# Calciatore_Rev_2_UP.net
KiCad netlist of a schematic drawn in EAGLE
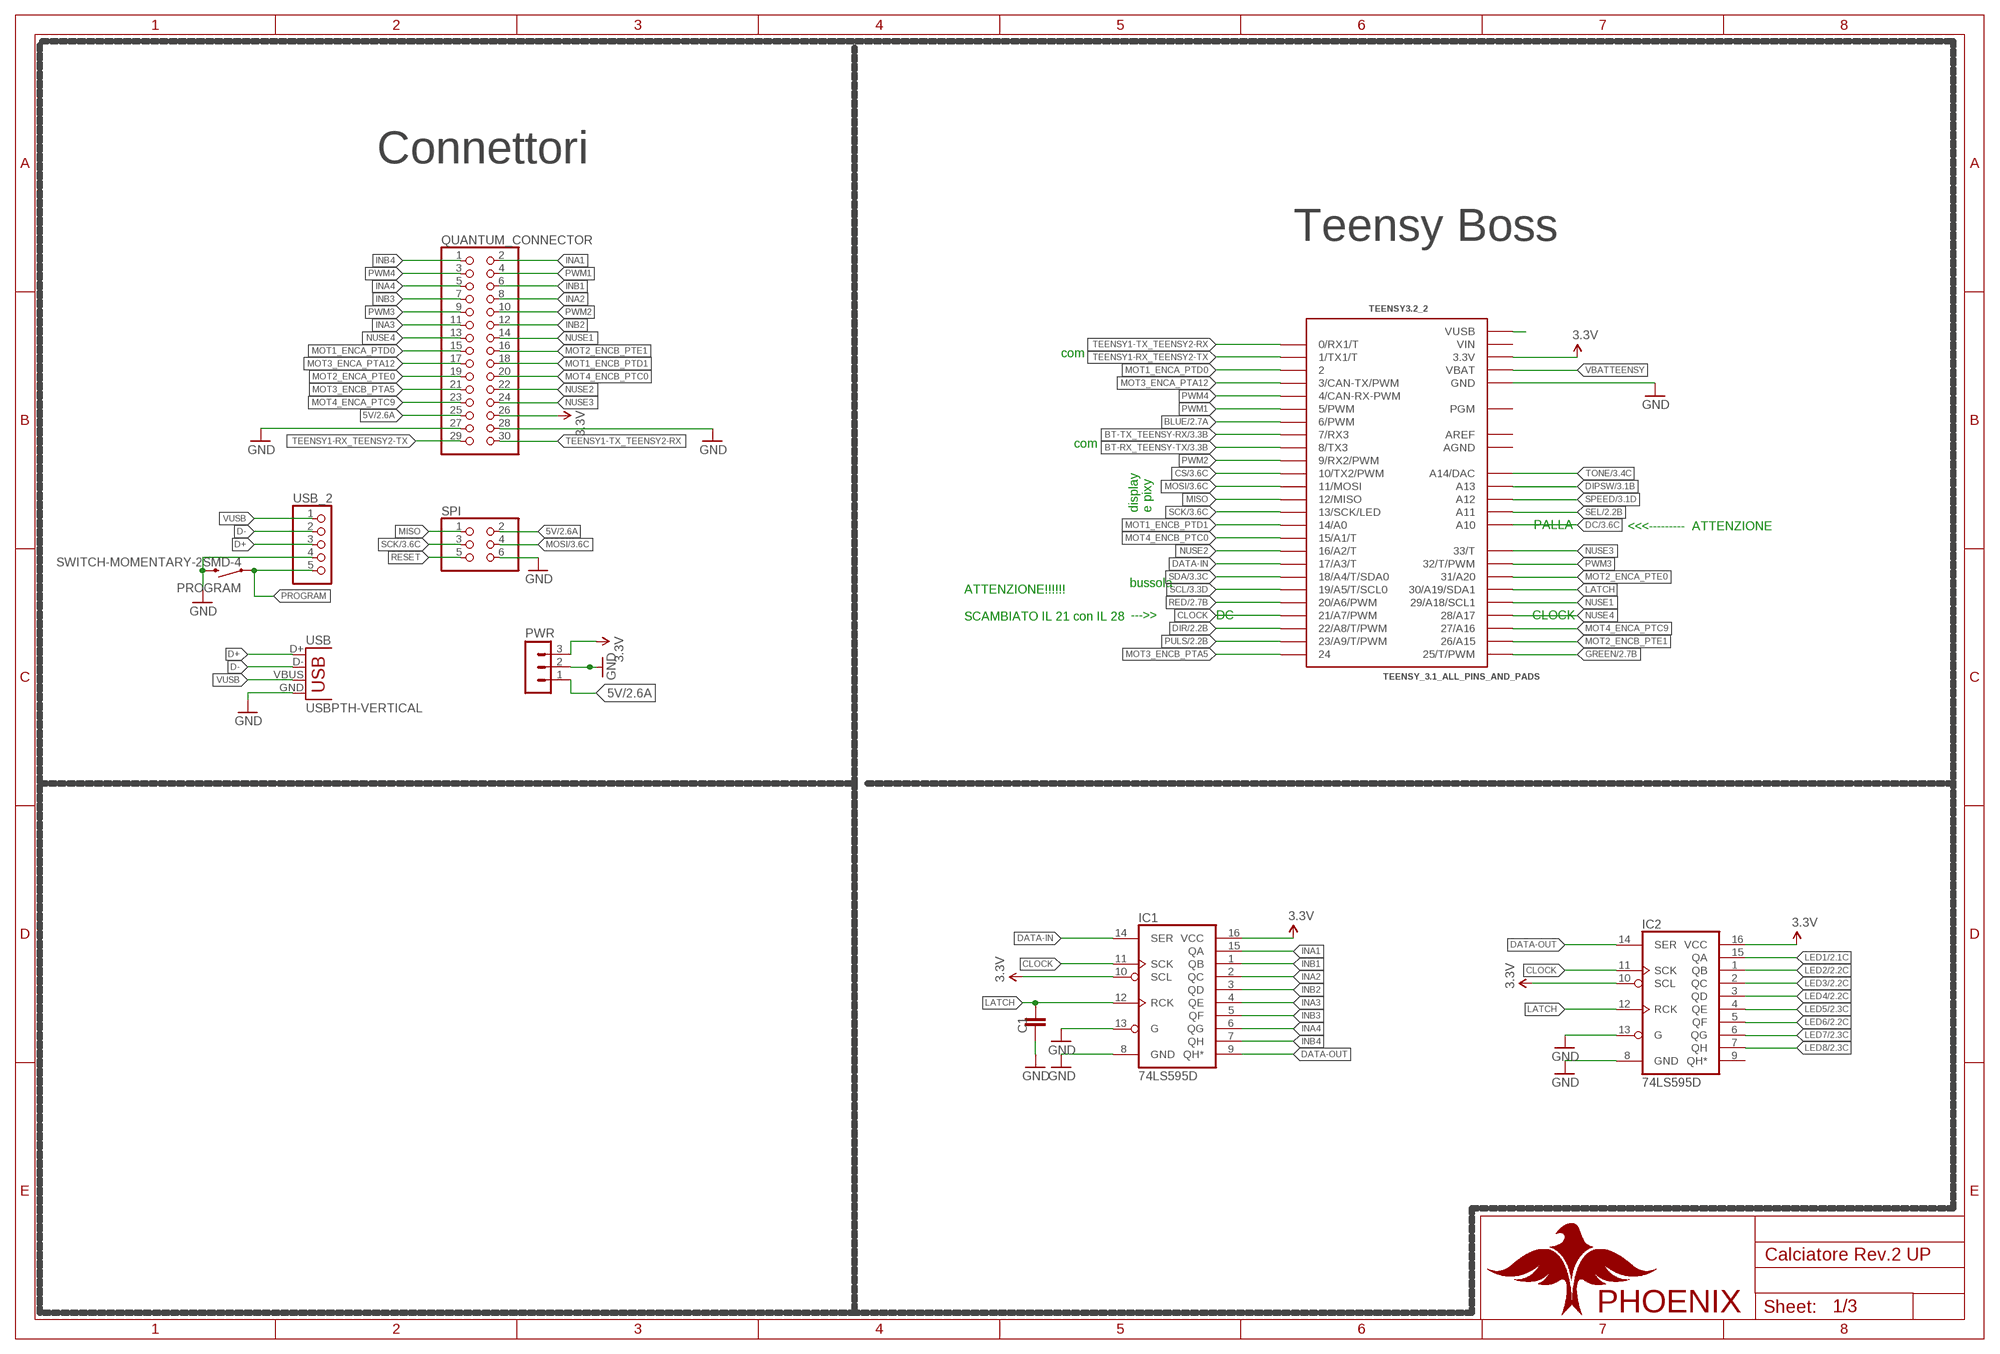
[diagram p0: schematic, sheet 1]
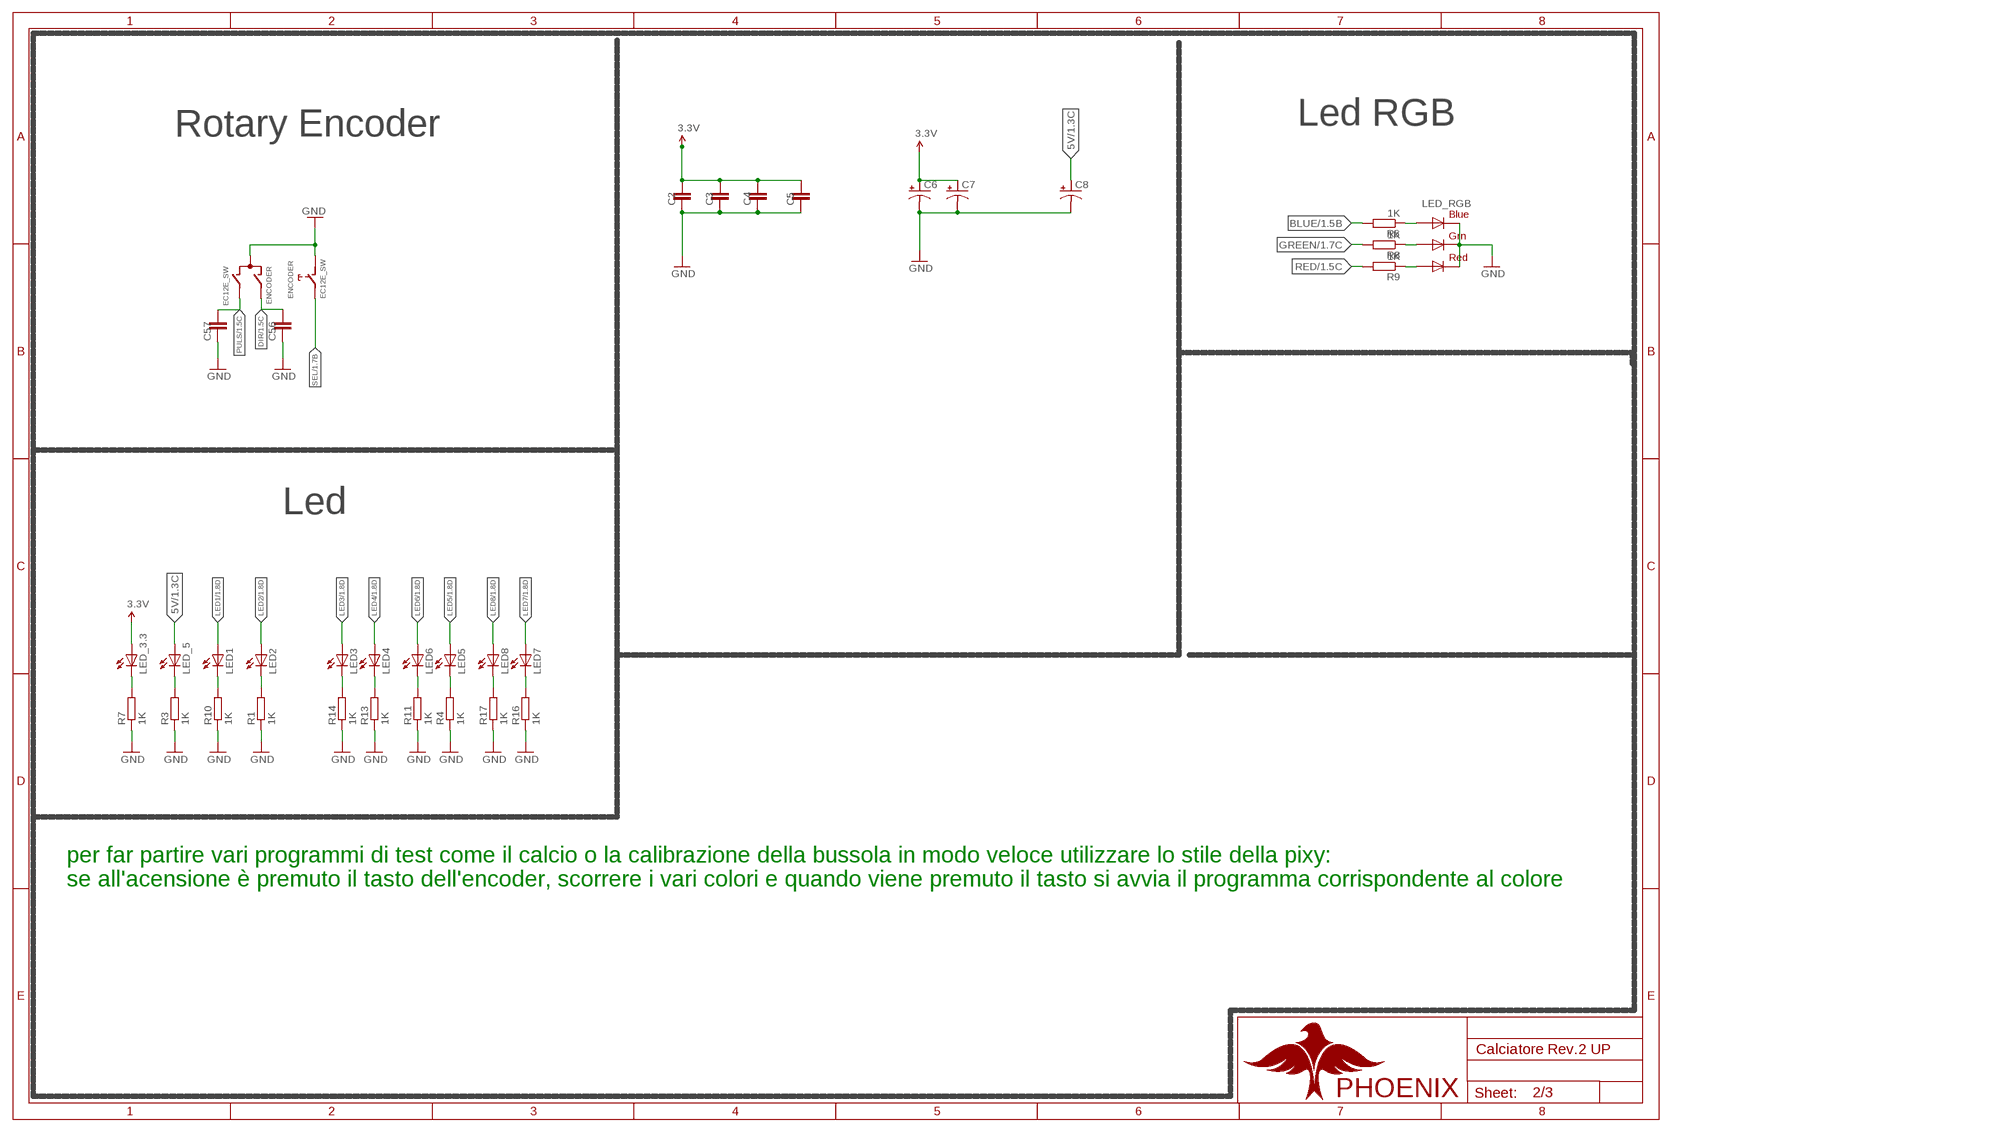
[diagram p1: schematic, sheet 2]
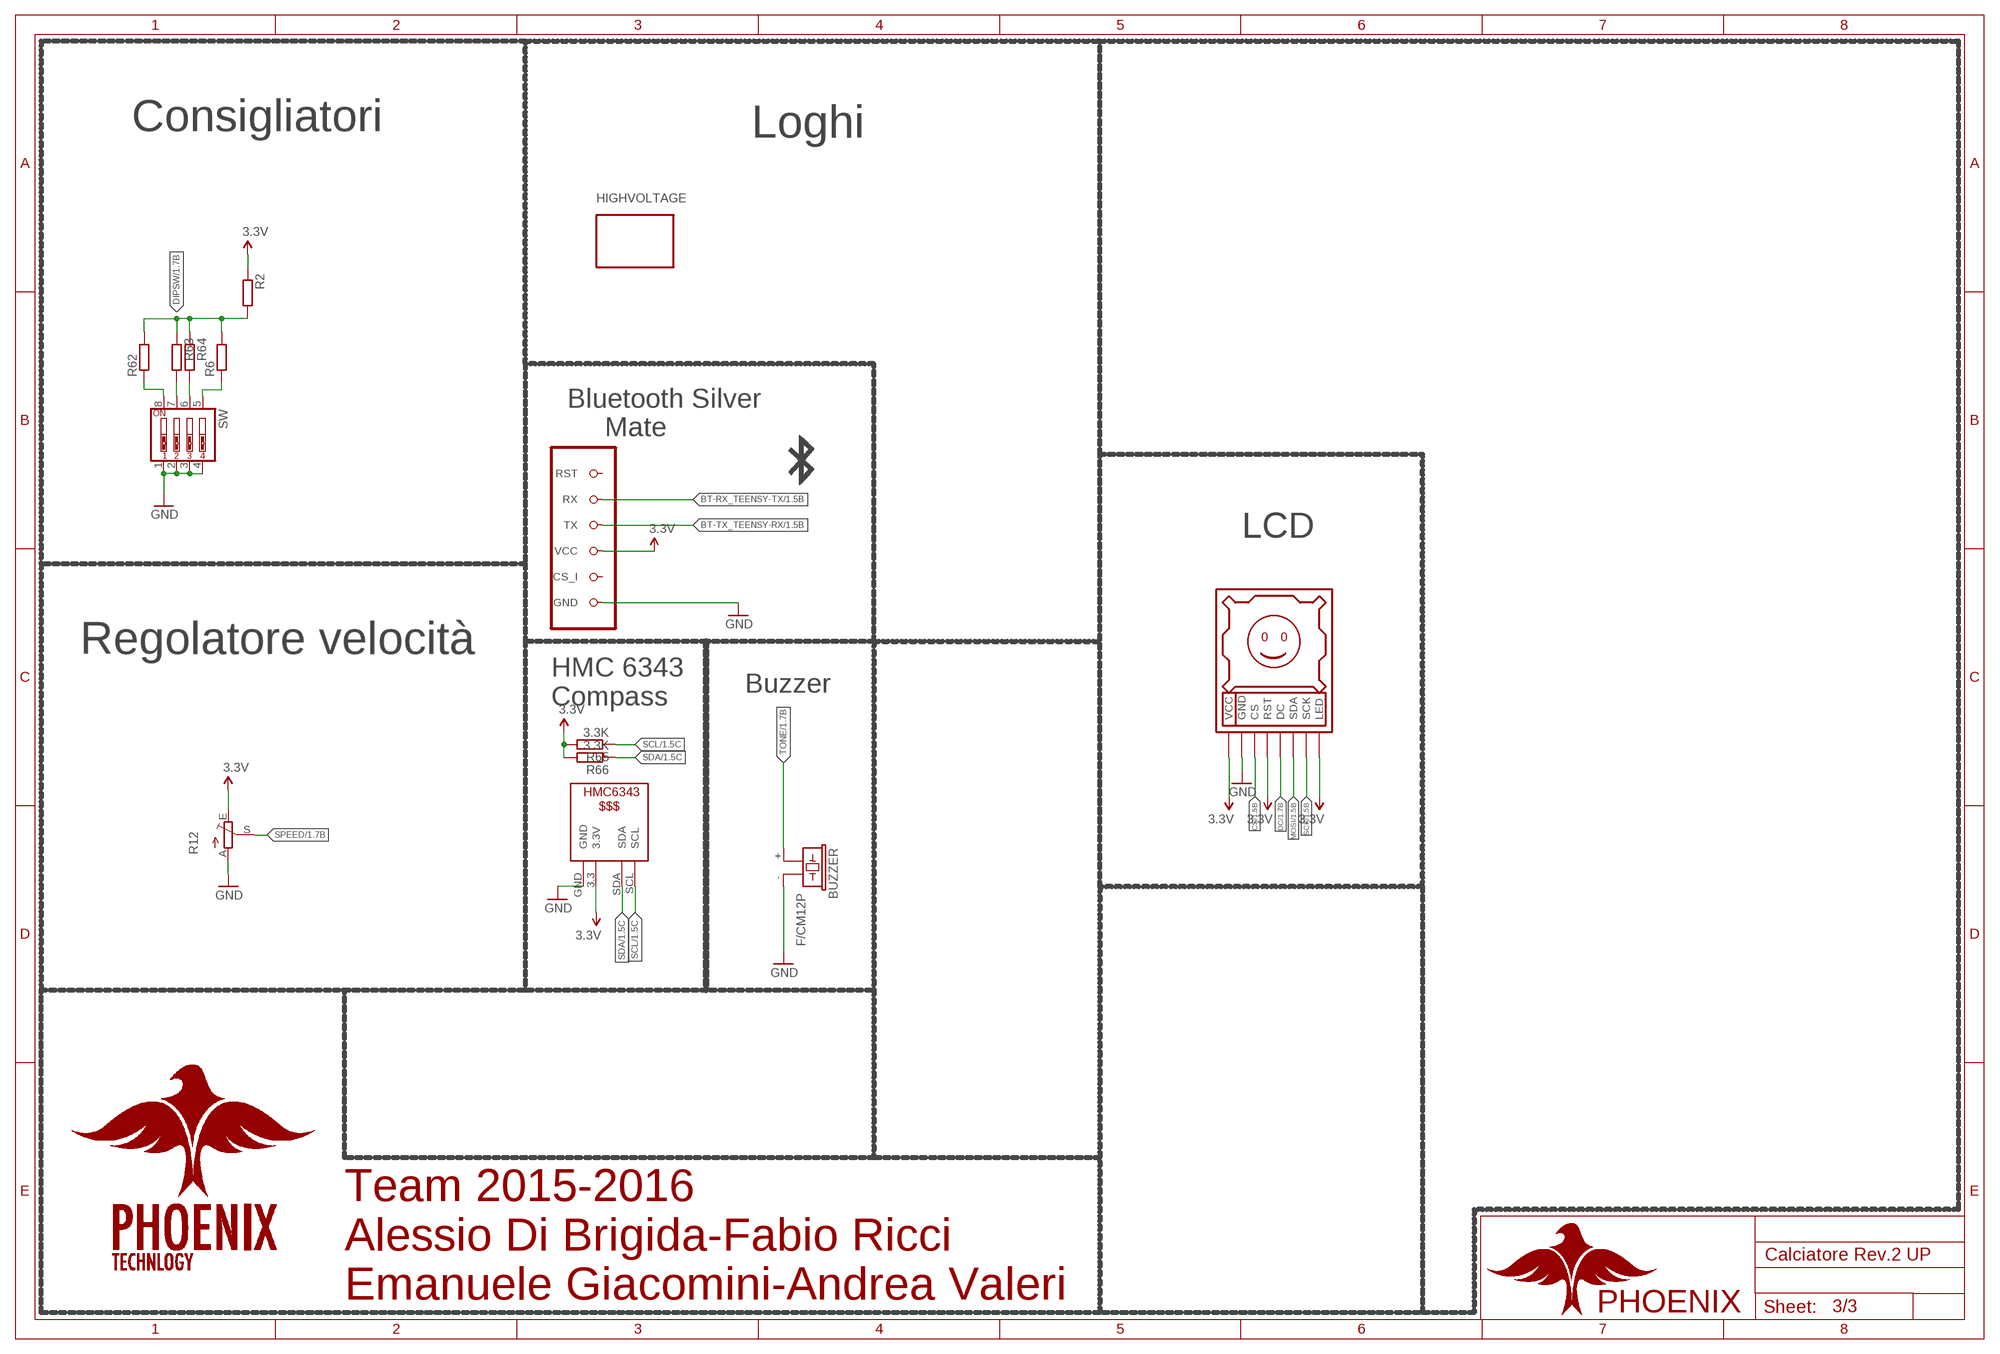
[diagram p2: schematic, sheet 3]

(export (version "E")
  (design (tool "Eeschema 10.0.6"))
  (components
    (comp (ref "BUZZER")
      (value "F/CM12P")
      (footprint "eagle-import:F_CM12P")
      (libsource (lib "eagle-import") (part "F/CM12P"))
    )
    (comp (ref "DISPLAY1")
      (value "DISPLAY128X128")
      (footprint "eagle-import:DISPLAY128X128")
      (libsource (lib "eagle-import") (part "DISPLAY128X128"))
    )
    (comp (ref "HIGHVOLTAGE")
      (value "LOGO")
      (footprint "eagle-import:LOGOHV")
      (libsource (lib "eagle-import") (part "LOGO"))
    )
    (comp (ref "R2")
      (value "10K")
      (footprint "eagle-import:M1206")
      (libsource (lib "eagle-import") (part "R-EU_M1206"))
    )
    (comp (ref "R6")
      (value "10K")
      (footprint "eagle-import:M1206")
      (libsource (lib "eagle-import") (part "R-EU_M1206"))
    )
    (comp (ref "R12")
      (value "TRIM_EU-S63P")
      (footprint "eagle-import:S63P")
      (libsource (lib "eagle-import") (part "TRIM_EU-S63P"))
    )
    (comp (ref "R62")
      (value "10K")
      (footprint "eagle-import:M1206")
      (libsource (lib "eagle-import") (part "R-EU_M1206"))
    )
    (comp (ref "R63")
      (value "10K")
      (footprint "eagle-import:M1206")
      (libsource (lib "eagle-import") (part "R-EU_M1206"))
    )
    (comp (ref "R64")
      (value "10K")
      (footprint "eagle-import:M1206")
      (libsource (lib "eagle-import") (part "R-EU_M1206"))
    )
    (comp (ref "R65")
      (value "3.3K")
      (footprint "eagle-import:M1206")
      (libsource (lib "eagle-import") (part "R-EU_M1206"))
    )
    (comp (ref "R66")
      (value "3.3K")
      (footprint "eagle-import:M1206")
      (libsource (lib "eagle-import") (part "R-EU_M1206"))
    )
    (comp (ref "SW")
      (value "SW_DIP-4")
      (footprint "eagle-import:EDG-04")
      (libsource (lib "eagle-import") (part "SW_DIP-4"))
    )
    (comp (ref "U$5")
      (value "HMC6343")
      (footprint "eagle-import:HMC6343")
      (libsource (lib "eagle-import") (part "HMC6343"))
    )
    (comp (ref "U$9")
      (value "BLUETOOTH")
      (footprint "eagle-import:BLUETOOTH")
      (libsource (lib "eagle-import") (part "BLUETOOTH"))
    )
    (comp (ref "C2")
      (value "C-EUC1206")
      (footprint "eagle-import:C1206")
      (libsource (lib "eagle-import") (part "C-EUC1206"))
    )
    (comp (ref "C3")
      (value "C-EUC1206")
      (footprint "eagle-import:C1206")
      (libsource (lib "eagle-import") (part "C-EUC1206"))
    )
    (comp (ref "C4")
      (value "C-EUC1206")
      (footprint "eagle-import:C1206")
      (libsource (lib "eagle-import") (part "C-EUC1206"))
    )
    (comp (ref "C5")
      (value "C-EUC1206")
      (footprint "eagle-import:C1206")
      (libsource (lib "eagle-import") (part "C-EUC1206"))
    )
    (comp (ref "C6")
      (value "CPOL-USE3.5-8")
      (footprint "eagle-import:E3,5-8")
      (libsource (lib "eagle-import") (part "CPOL-USE3.5-8"))
    )
    (comp (ref "C7")
      (value "CPOL-USE3.5-8")
      (footprint "eagle-import:E3,5-8")
      (libsource (lib "eagle-import") (part "CPOL-USE3.5-8"))
    )
    (comp (ref "C8")
      (value "CPOL-USE3.5-8")
      (footprint "eagle-import:E3,5-8")
      (libsource (lib "eagle-import") (part "CPOL-USE3.5-8"))
    )
    (comp (ref "C56")
      (value "C-EUC1206")
      (footprint "eagle-import:C1206")
      (libsource (lib "eagle-import") (part "C-EUC1206"))
    )
    (comp (ref "C57")
      (value "C-EUC1206")
      (footprint "eagle-import:C1206")
      (libsource (lib "eagle-import") (part "C-EUC1206"))
    )
    (comp (ref "ENCODER")
      (value "EC12E_SW")
      (footprint "eagle-import:ALPS_EC12E_SW")
      (fields (field (name "MPN") "EC12E2424407"))
      (libsource (lib "eagle-import") (part "EC12E_SW"))
    )
    (comp (ref "LED1")
      (value "LEDSMT1206")
      (footprint "eagle-import:1206")
      (libsource (lib "eagle-import") (part "LEDSMT1206"))
    )
    (comp (ref "LED2")
      (value "LEDSMT1206")
      (footprint "eagle-import:1206")
      (libsource (lib "eagle-import") (part "LEDSMT1206"))
    )
    (comp (ref "LED3")
      (value "LEDSMT1206")
      (footprint "eagle-import:1206")
      (libsource (lib "eagle-import") (part "LEDSMT1206"))
    )
    (comp (ref "LED4")
      (value "LEDSMT1206")
      (footprint "eagle-import:1206")
      (libsource (lib "eagle-import") (part "LEDSMT1206"))
    )
    (comp (ref "LED5")
      (value "LEDSMT1206")
      (footprint "eagle-import:1206")
      (libsource (lib "eagle-import") (part "LEDSMT1206"))
    )
    (comp (ref "LED6")
      (value "LEDSMT1206")
      (footprint "eagle-import:1206")
      (libsource (lib "eagle-import") (part "LEDSMT1206"))
    )
    (comp (ref "LED7")
      (value "LEDSMT1206")
      (footprint "eagle-import:1206")
      (libsource (lib "eagle-import") (part "LEDSMT1206"))
    )
    (comp (ref "LED8")
      (value "LEDSMT1206")
      (footprint "eagle-import:1206")
      (libsource (lib "eagle-import") (part "LEDSMT1206"))
    )
    (comp (ref "LED_3.3")
      (value "LEDSMT1206")
      (footprint "eagle-import:1206")
      (libsource (lib "eagle-import") (part "LEDSMT1206"))
    )
    (comp (ref "LED_5")
      (value "LEDSMT1206")
      (footprint "eagle-import:1206")
      (libsource (lib "eagle-import") (part "LEDSMT1206"))
    )
    (comp (ref "LED_RGB")
      (value "RGBLED5050")
      (footprint "eagle-import:RGBLED5050")
      (libsource (lib "eagle-import") (part "RGBLED5050"))
    )
    (comp (ref "R1")
      (value "1K")
      (footprint "eagle-import:M1206")
      (libsource (lib "eagle-import") (part "resistor_R-EU_M1206"))
    )
    (comp (ref "R3")
      (value "1K")
      (footprint "eagle-import:M1206")
      (libsource (lib "eagle-import") (part "resistor_R-EU_M1206"))
    )
    (comp (ref "R4")
      (value "1K")
      (footprint "eagle-import:M1206")
      (libsource (lib "eagle-import") (part "resistor_R-EU_M1206"))
    )
    (comp (ref "R5")
      (value "1K")
      (footprint "eagle-import:M1206")
      (libsource (lib "eagle-import") (part "resistor_R-EU_M1206"))
    )
    (comp (ref "R7")
      (value "1K")
      (footprint "eagle-import:M1206")
      (libsource (lib "eagle-import") (part "resistor_R-EU_M1206"))
    )
    (comp (ref "R8")
      (value "1K")
      (footprint "eagle-import:M1206")
      (libsource (lib "eagle-import") (part "resistor_R-EU_M1206"))
    )
    (comp (ref "R9")
      (value "1K")
      (footprint "eagle-import:M1206")
      (libsource (lib "eagle-import") (part "resistor_R-EU_M1206"))
    )
    (comp (ref "R10")
      (value "1K")
      (footprint "eagle-import:M1206")
      (libsource (lib "eagle-import") (part "resistor_R-EU_M1206"))
    )
    (comp (ref "R11")
      (value "1K")
      (footprint "eagle-import:M1206")
      (libsource (lib "eagle-import") (part "resistor_R-EU_M1206"))
    )
    (comp (ref "R13")
      (value "1K")
      (footprint "eagle-import:M1206")
      (libsource (lib "eagle-import") (part "resistor_R-EU_M1206"))
    )
    (comp (ref "R14")
      (value "1K")
      (footprint "eagle-import:M1206")
      (libsource (lib "eagle-import") (part "resistor_R-EU_M1206"))
    )
    (comp (ref "R16")
      (value "1K")
      (footprint "eagle-import:M1206")
      (libsource (lib "eagle-import") (part "resistor_R-EU_M1206"))
    )
    (comp (ref "R17")
      (value "1K")
      (footprint "eagle-import:M1206")
      (libsource (lib "eagle-import") (part "resistor_R-EU_M1206"))
    )
    (comp (ref "C1")
      (value "C-EUC1206")
      (footprint "eagle-import:C1206")
      (libsource (lib "eagle-import") (part "C-EUC1206"))
    )
    (comp (ref "IC1")
      (value "74LS595D")
      (footprint "eagle-import:SO16")
      (libsource (lib "eagle-import") (part "74595DLS"))
    )
    (comp (ref "IC2")
      (value "74LS595D")
      (footprint "eagle-import:SO16")
      (libsource (lib "eagle-import") (part "74595DLS"))
    )
    (comp (ref "PROGRAM")
      (value "SWITCH-MOMENTARY-2SMD-4")
      (footprint "eagle-import:TACTILE_SWITCH_TALL")
      (libsource (lib "eagle-import") (part "SWITCH-MOMENTARY-2SMD-4"))
    )
    (comp (ref "PWR")
      (value "MA03-1")
      (footprint "eagle-import:MA03-1")
      (libsource (lib "eagle-import") (part "MA03-1"))
    )
    (comp (ref "QUANTUM_CONNECTOR")
      (value "PINHD-2X15")
      (footprint "eagle-import:2X15")
      (libsource (lib "eagle-import") (part "PINHD-2X15"))
    )
    (comp (ref "SPI")
      (value "PINHD-2X3")
      (footprint "eagle-import:2X03")
      (libsource (lib "eagle-import") (part "PINHD-2X3"))
    )
    (comp (ref "TEENSY3.2_2")
      (value "TEENSY_3.1_ALL_PINS_AND_PADS")
      (footprint "eagle-import:TEENSY3_ALL_PINS_&_PADS")
      (libsource (lib "eagle-import") (part "TEENSY_3.1_ALL_PINS_AND_PADS"))
    )
    (comp (ref "USB")
      (value "USBPTH-VERTICAL")
      (footprint "eagle-import:USB-B-PTH-VERTICAL")
      (libsource (lib "eagle-import") (part "USBPTH-VERTICAL"))
    )
    (comp (ref "USB_2")
      (value "PINHD-1X5")
      (footprint "eagle-import:1X05")
      (libsource (lib "eagle-import") (part "PINHD-1X5"))
    )
  )
  (nets
    (net (code "1") (name "3.3V") (class "Default")
      (node (ref "C2") (pin "2") (pinfunction "2_2") (pintype "passive"))
      (node (ref "C3") (pin "2") (pinfunction "2_2") (pintype "passive"))
      (node (ref "C4") (pin "2") (pinfunction "2_2") (pintype "passive"))
      (node (ref "C5") (pin "2") (pinfunction "2_2") (pintype "passive"))
      (node (ref "C6") (pin "+") (pinfunction "+_+") (pintype "passive"))
      (node (ref "C7") (pin "+") (pinfunction "+_+") (pintype "passive"))
      (node (ref "DISPLAY1") (pin "LED") (pinfunction "LED_LED") (pintype "input"))
      (node (ref "DISPLAY1") (pin "RST") (pinfunction "RST_RST") (pintype "input"))
      (node (ref "DISPLAY1") (pin "VCC") (pinfunction "VCC_VCC") (pintype "power_in"))
      (node (ref "IC1") (pin "10") (pinfunction "SCL_10") (pintype "input"))
      (node (ref "IC1") (pin "16") (pinfunction "VCC_16") (pintype "power_in"))
      (node (ref "IC2") (pin "10") (pinfunction "SCL_10") (pintype "input"))
      (node (ref "IC2") (pin "16") (pinfunction "VCC_16") (pintype "power_in"))
      (node (ref "LED_3.3") (pin "A") (pinfunction "A_A") (pintype "passive"))
      (node (ref "PWR") (pin "3") (pinfunction "3_3") (pintype "passive"))
      (node (ref "QUANTUM_CONNECTOR") (pin "26") (pinfunction "26_26") (pintype "passive"))
      (node (ref "R12") (pin "E") (pinfunction "E_E") (pintype "passive"))
      (node (ref "R2") (pin "1") (pinfunction "1_1") (pintype "passive"))
      (node (ref "R65") (pin "2") (pinfunction "2_2") (pintype "passive"))
      (node (ref "R66") (pin "2") (pinfunction "2_2") (pintype "passive"))
      (node (ref "TEENSY3.2_2") (pin "3.3V") (pinfunction "3.3V_3.3V") (pintype "power_in"))
      (node (ref "TEENSY3.2_2") (pin "3.3V1") (pinfunction "3.3V_3.3V1") (pintype "power_in"))
      (node (ref "TEENSY3.2_2") (pin "3.3V2") (pinfunction "3.3V_3.3V2") (pintype "power_in"))
      (node (ref "U$5") (pin "3.3") (pinfunction "3.3V_3.3") (pintype "bidirectional"))
      (node (ref "U$9") (pin "VCC") (pinfunction "VCC_VCC") (pintype "power_in"))
    )
    (net (code "2") (name "5V") (class "Default")
      (node (ref "C8") (pin "+") (pinfunction "+_+") (pintype "passive"))
      (node (ref "LED_5") (pin "A") (pinfunction "A_A") (pintype "passive"))
      (node (ref "PWR") (pin "1") (pinfunction "1_1") (pintype "passive"))
      (node (ref "QUANTUM_CONNECTOR") (pin "25") (pinfunction "25_25") (pintype "passive"))
      (node (ref "SPI") (pin "2") (pinfunction "2_2") (pintype "passive"))
    )
    (net (code "3") (name "AGND") (class "Default")
      (node (ref "TEENSY3.2_2") (pin "AGND") (pinfunction "AGND_AGND") (pintype "power_in"))
    )
    (net (code "4") (name "AREF") (class "Default")
      (node (ref "TEENSY3.2_2") (pin "AREF") (pinfunction "AREF_AREF") (pintype "power_in"))
    )
    (net (code "5") (name "BLUE") (class "Default")
      (node (ref "R5") (pin "2") (pinfunction "2_2") (pintype "passive"))
      (node (ref "TEENSY3.2_2") (pin "6") (pinfunction "6/PWM_6") (pintype "bidirectional"))
    )
    (net (code "6") (name "BT-RX_TEENSY-TX") (class "Default")
      (node (ref "TEENSY3.2_2") (pin "8") (pinfunction "8/TX3_8") (pintype "bidirectional"))
      (node (ref "U$9") (pin "RX") (pinfunction "RX_RX") (pintype "input"))
    )
    (net (code "7") (name "BT-TX_TEENSY-RX") (class "Default")
      (node (ref "TEENSY3.2_2") (pin "7") (pinfunction "7/RX3_7") (pintype "bidirectional"))
      (node (ref "U$9") (pin "TX") (pinfunction "TX_TX") (pintype "output"))
    )
    (net (code "8") (name "CLOCK") (class "Default")
      (node (ref "IC1") (pin "11") (pinfunction "SCK_11") (pintype "input"))
      (node (ref "IC2") (pin "11") (pinfunction "SCK_11") (pintype "input"))
      (node (ref "TEENSY3.2_2") (pin "21/A7") (pinfunction "21/A7/PWM_21/A7") (pintype "bidirectional"))
    )
    (net (code "9") (name "CS") (class "Default")
      (node (ref "DISPLAY1") (pin "CS") (pinfunction "CS_CS") (pintype "bidirectional"))
      (node (ref "TEENSY3.2_2") (pin "10") (pinfunction "10/TX2/PWM_10") (pintype "bidirectional"))
    )
    (net (code "10") (name "D+") (class "Default")
      (node (ref "USB") (pin "D+") (pinfunction "D+_D+") (pintype "bidirectional"))
      (node (ref "USB_2") (pin "3") (pinfunction "3_3") (pintype "passive"))
    )
    (net (code "11") (name "D-") (class "Default")
      (node (ref "USB") (pin "D-") (pinfunction "D-_D-") (pintype "bidirectional"))
      (node (ref "USB_2") (pin "2") (pinfunction "2_2") (pintype "passive"))
    )
    (net (code "12") (name "DATA-IN") (class "Default")
      (node (ref "IC1") (pin "14") (pinfunction "SER_14") (pintype "input"))
      (node (ref "TEENSY3.2_2") (pin "17/A3") (pinfunction "17/A3/T_17/A3") (pintype "bidirectional"))
    )
    (net (code "13") (name "DATA-OUT") (class "Default")
      (node (ref "IC1") (pin "9") (pinfunction "QH*_9") (pintype "tri_state"))
      (node (ref "IC2") (pin "14") (pinfunction "SER_14") (pintype "input"))
    )
    (net (code "14") (name "DC") (class "Default")
      (node (ref "DISPLAY1") (pin "DC") (pinfunction "DC_DC") (pintype "bidirectional"))
      (node (ref "TEENSY3.2_2") (pin "A10") (pinfunction "A10_A10") (pintype "bidirectional"))
    )
    (net (code "15") (name "DIPSW") (class "Default")
      (node (ref "R2") (pin "2") (pinfunction "2_2") (pintype "passive"))
      (node (ref "R6") (pin "2") (pinfunction "2_2") (pintype "passive"))
      (node (ref "R62") (pin "2") (pinfunction "2_2") (pintype "passive"))
      (node (ref "R63") (pin "1") (pinfunction "1_1") (pintype "passive"))
      (node (ref "R64") (pin "1") (pinfunction "1_1") (pintype "passive"))
      (node (ref "TEENSY3.2_2") (pin "A13") (pinfunction "A13_A13") (pintype "bidirectional"))
    )
    (net (code "16") (name "DIR") (class "Default")
      (node (ref "C56") (pin "2") (pinfunction "2_2") (pintype "passive"))
      (node (ref "ENCODER") (pin "A") (pinfunction "A_A") (pintype "passive"))
      (node (ref "TEENSY3.2_2") (pin "22/A8") (pinfunction "22/A8/T/PWM_22/A8") (pintype "bidirectional"))
    )
    (net (code "17") (name "GND") (class "Default")
      (node (ref "BUZZER") (pin "-") (pinfunction "2_-") (pintype "passive"))
      (node (ref "C1") (pin "1") (pinfunction "1_1") (pintype "passive"))
      (node (ref "C2") (pin "1") (pinfunction "1_1") (pintype "passive"))
      (node (ref "C3") (pin "1") (pinfunction "1_1") (pintype "passive"))
      (node (ref "C4") (pin "1") (pinfunction "1_1") (pintype "passive"))
      (node (ref "C5") (pin "1") (pinfunction "1_1") (pintype "passive"))
      (node (ref "C56") (pin "1") (pinfunction "1_1") (pintype "passive"))
      (node (ref "C57") (pin "1") (pinfunction "1_1") (pintype "passive"))
      (node (ref "C6") (pin "-") (pinfunction "-_-") (pintype "passive"))
      (node (ref "C7") (pin "-") (pinfunction "-_-") (pintype "passive"))
      (node (ref "C8") (pin "-") (pinfunction "-_-") (pintype "passive"))
      (node (ref "DISPLAY1") (pin "GND") (pinfunction "GND_GND") (pintype "power_in"))
      (node (ref "ENCODER") (pin "C") (pinfunction "C_C") (pintype "passive"))
      (node (ref "ENCODER") (pin "D") (pinfunction "1_D") (pintype "passive"))
      (node (ref "IC1") (pin "13") (pinfunction "G_13") (pintype "input"))
      (node (ref "IC1") (pin "8") (pinfunction "GND_8") (pintype "power_in"))
      (node (ref "IC2") (pin "13") (pinfunction "G_13") (pintype "input"))
      (node (ref "IC2") (pin "8") (pinfunction "GND_8") (pintype "power_in"))
      (node (ref "LED_RGB") (pin "4") (pinfunction "BLUE_C_4") (pintype "bidirectional"))
      (node (ref "LED_RGB") (pin "5") (pinfunction "RED_C_5") (pintype "bidirectional"))
      (node (ref "LED_RGB") (pin "6") (pinfunction "GREEN_C_6") (pintype "bidirectional"))
      (node (ref "PROGRAM") (pin "B2") (pinfunction "2_B2") (pintype "passive"))
      (node (ref "PWR") (pin "2") (pinfunction "2_2") (pintype "passive"))
      (node (ref "QUANTUM_CONNECTOR") (pin "27") (pinfunction "27_27") (pintype "passive"))
      (node (ref "QUANTUM_CONNECTOR") (pin "28") (pinfunction "28_28") (pintype "passive"))
      (node (ref "R1") (pin "1") (pinfunction "1_1") (pintype "passive"))
      (node (ref "R10") (pin "1") (pinfunction "1_1") (pintype "passive"))
      (node (ref "R11") (pin "1") (pinfunction "1_1") (pintype "passive"))
      (node (ref "R12") (pin "A") (pinfunction "A_A") (pintype "passive"))
      (node (ref "R13") (pin "1") (pinfunction "1_1") (pintype "passive"))
      (node (ref "R14") (pin "1") (pinfunction "1_1") (pintype "passive"))
      (node (ref "R16") (pin "1") (pinfunction "1_1") (pintype "passive"))
      (node (ref "R17") (pin "1") (pinfunction "1_1") (pintype "passive"))
      (node (ref "R3") (pin "1") (pinfunction "1_1") (pintype "passive"))
      (node (ref "R4") (pin "1") (pinfunction "1_1") (pintype "passive"))
      (node (ref "R7") (pin "1") (pinfunction "1_1") (pintype "passive"))
      (node (ref "SPI") (pin "6") (pinfunction "6_6") (pintype "passive"))
      (node (ref "SW") (pin "1") (pinfunction "1_1") (pintype "passive"))
      (node (ref "SW") (pin "2") (pinfunction "2_2") (pintype "passive"))
      (node (ref "SW") (pin "3") (pinfunction "3_3") (pintype "passive"))
      (node (ref "SW") (pin "4") (pinfunction "4_4") (pintype "passive"))
      (node (ref "TEENSY3.2_2") (pin "GND") (pinfunction "GND_GND") (pintype "power_in"))
      (node (ref "TEENSY3.2_2") (pin "GND1") (pinfunction "GND_GND1") (pintype "power_in"))
      (node (ref "TEENSY3.2_2") (pin "GND2") (pinfunction "GND_GND2") (pintype "power_in"))
      (node (ref "U$5") (pin "GND") (pinfunction "GND_GND") (pintype "bidirectional"))
      (node (ref "U$9") (pin "GND") (pinfunction "GND_GND") (pintype "power_in"))
      (node (ref "USB") (pin "GND") (pinfunction "GND_GND") (pintype "bidirectional"))
      (node (ref "USB_2") (pin "4") (pinfunction "4_4") (pintype "passive"))
    )
    (net (code "18") (name "GREEN") (class "Default")
      (node (ref "R8") (pin "2") (pinfunction "2_2") (pintype "passive"))
      (node (ref "TEENSY3.2_2") (pin "25") (pinfunction "25/T/PWM_25") (pintype "bidirectional"))
    )
    (net (code "19") (name "INA1") (class "Default")
      (node (ref "IC1") (pin "15") (pinfunction "QA_15") (pintype "tri_state"))
      (node (ref "QUANTUM_CONNECTOR") (pin "2") (pinfunction "2_2") (pintype "passive"))
    )
    (net (code "20") (name "INA2") (class "Default")
      (node (ref "IC1") (pin "2") (pinfunction "QC_2") (pintype "tri_state"))
      (node (ref "QUANTUM_CONNECTOR") (pin "8") (pinfunction "8_8") (pintype "passive"))
    )
    (net (code "21") (name "INA3") (class "Default")
      (node (ref "IC1") (pin "4") (pinfunction "QE_4") (pintype "tri_state"))
      (node (ref "QUANTUM_CONNECTOR") (pin "11") (pinfunction "11_11") (pintype "passive"))
    )
    (net (code "22") (name "INA4") (class "Default")
      (node (ref "IC1") (pin "6") (pinfunction "QG_6") (pintype "tri_state"))
      (node (ref "QUANTUM_CONNECTOR") (pin "5") (pinfunction "5_5") (pintype "passive"))
    )
    (net (code "23") (name "INB1") (class "Default")
      (node (ref "IC1") (pin "1") (pinfunction "QB_1") (pintype "tri_state"))
      (node (ref "QUANTUM_CONNECTOR") (pin "6") (pinfunction "6_6") (pintype "passive"))
    )
    (net (code "24") (name "INB2") (class "Default")
      (node (ref "IC1") (pin "3") (pinfunction "QD_3") (pintype "tri_state"))
      (node (ref "QUANTUM_CONNECTOR") (pin "12") (pinfunction "12_12") (pintype "passive"))
    )
    (net (code "25") (name "INB3") (class "Default")
      (node (ref "IC1") (pin "5") (pinfunction "QF_5") (pintype "tri_state"))
      (node (ref "QUANTUM_CONNECTOR") (pin "7") (pinfunction "7_7") (pintype "passive"))
    )
    (net (code "26") (name "INB4") (class "Default")
      (node (ref "IC1") (pin "7") (pinfunction "QH_7") (pintype "tri_state"))
      (node (ref "QUANTUM_CONNECTOR") (pin "1") (pinfunction "1_1") (pintype "passive"))
    )
    (net (code "27") (name "LATCH") (class "Default")
      (node (ref "C1") (pin "2") (pinfunction "2_2") (pintype "passive"))
      (node (ref "IC1") (pin "12") (pinfunction "RCK_12") (pintype "input"))
      (node (ref "IC2") (pin "12") (pinfunction "RCK_12") (pintype "input"))
      (node (ref "TEENSY3.2_2") (pin "30") (pinfunction "30/A19/SDA1_30") (pintype "bidirectional"))
    )
    (net (code "28") (name "LED1") (class "Default")
      (node (ref "IC2") (pin "15") (pinfunction "QA_15") (pintype "tri_state"))
      (node (ref "LED1") (pin "A") (pinfunction "A_A") (pintype "passive"))
    )
    (net (code "29") (name "LED2") (class "Default")
      (node (ref "IC2") (pin "1") (pinfunction "QB_1") (pintype "tri_state"))
      (node (ref "LED2") (pin "A") (pinfunction "A_A") (pintype "passive"))
    )
    (net (code "30") (name "LED3") (class "Default")
      (node (ref "IC2") (pin "2") (pinfunction "QC_2") (pintype "tri_state"))
      (node (ref "LED3") (pin "A") (pinfunction "A_A") (pintype "passive"))
    )
    (net (code "31") (name "LED4") (class "Default")
      (node (ref "IC2") (pin "3") (pinfunction "QD_3") (pintype "tri_state"))
      (node (ref "LED4") (pin "A") (pinfunction "A_A") (pintype "passive"))
    )
    (net (code "32") (name "LED5") (class "Default")
      (node (ref "IC2") (pin "4") (pinfunction "QE_4") (pintype "tri_state"))
      (node (ref "LED5") (pin "A") (pinfunction "A_A") (pintype "passive"))
    )
    (net (code "33") (name "LED6") (class "Default")
      (node (ref "IC2") (pin "5") (pinfunction "QF_5") (pintype "tri_state"))
      (node (ref "LED6") (pin "A") (pinfunction "A_A") (pintype "passive"))
    )
    (net (code "34") (name "LED7") (class "Default")
      (node (ref "IC2") (pin "6") (pinfunction "QG_6") (pintype "tri_state"))
      (node (ref "LED7") (pin "A") (pinfunction "A_A") (pintype "passive"))
    )
    (net (code "35") (name "LED8") (class "Default")
      (node (ref "IC2") (pin "7") (pinfunction "QH_7") (pintype "tri_state"))
      (node (ref "LED8") (pin "A") (pinfunction "A_A") (pintype "passive"))
    )
    (net (code "36") (name "MISO") (class "Default")
      (node (ref "SPI") (pin "1") (pinfunction "1_1") (pintype "passive"))
      (node (ref "TEENSY3.2_2") (pin "12") (pinfunction "12/MISO_12") (pintype "bidirectional"))
    )
    (net (code "37") (name "MOSI") (class "Default")
      (node (ref "DISPLAY1") (pin "SDA") (pinfunction "SDA_SDA") (pintype "bidirectional"))
      (node (ref "SPI") (pin "4") (pinfunction "4_4") (pintype "passive"))
      (node (ref "TEENSY3.2_2") (pin "11") (pinfunction "11/MOSI_11") (pintype "bidirectional"))
    )
    (net (code "38") (name "MOT1_ENCA_PTD0") (class "Default")
      (node (ref "QUANTUM_CONNECTOR") (pin "15") (pinfunction "15_15") (pintype "passive"))
      (node (ref "TEENSY3.2_2") (pin "2") (pinfunction "2_2") (pintype "bidirectional"))
    )
    (net (code "39") (name "MOT1_ENCB_PTD1") (class "Default")
      (node (ref "QUANTUM_CONNECTOR") (pin "18") (pinfunction "18_18") (pintype "passive"))
      (node (ref "TEENSY3.2_2") (pin "14/A0") (pinfunction "14/A0_14/A0") (pintype "bidirectional"))
    )
    (net (code "40") (name "MOT2_ENCA_PTE0") (class "Default")
      (node (ref "QUANTUM_CONNECTOR") (pin "19") (pinfunction "19_19") (pintype "passive"))
      (node (ref "TEENSY3.2_2") (pin "31") (pinfunction "31/A20_31") (pintype "bidirectional"))
    )
    (net (code "41") (name "MOT2_ENCB_PTE1") (class "Default")
      (node (ref "QUANTUM_CONNECTOR") (pin "16") (pinfunction "16_16") (pintype "passive"))
      (node (ref "TEENSY3.2_2") (pin "26") (pinfunction "26/A15_26") (pintype "bidirectional"))
    )
    (net (code "42") (name "MOT3_ENCA_PTA12") (class "Default")
      (node (ref "QUANTUM_CONNECTOR") (pin "17") (pinfunction "17_17") (pintype "passive"))
      (node (ref "TEENSY3.2_2") (pin "3") (pinfunction "3/CAN-TX/PWM_3") (pintype "bidirectional"))
    )
    (net (code "43") (name "MOT3_ENCB_PTA5") (class "Default")
      (node (ref "QUANTUM_CONNECTOR") (pin "21") (pinfunction "21_21") (pintype "passive"))
      (node (ref "TEENSY3.2_2") (pin "24") (pinfunction "24_24") (pintype "bidirectional"))
    )
    (net (code "44") (name "MOT4_ENCA_PTC9") (class "Default")
      (node (ref "QUANTUM_CONNECTOR") (pin "23") (pinfunction "23_23") (pintype "passive"))
      (node (ref "TEENSY3.2_2") (pin "27") (pinfunction "27/A16_27") (pintype "bidirectional"))
    )
    (net (code "45") (name "MOT4_ENCB_PTC0") (class "Default")
      (node (ref "QUANTUM_CONNECTOR") (pin "20") (pinfunction "20_20") (pintype "passive"))
      (node (ref "TEENSY3.2_2") (pin "15/A1") (pinfunction "15/A1/T_15/A1") (pintype "bidirectional"))
    )
    (net (code "46") (name "NUSE1") (class "Default")
      (node (ref "QUANTUM_CONNECTOR") (pin "14") (pinfunction "14_14") (pintype "passive"))
      (node (ref "TEENSY3.2_2") (pin "29") (pinfunction "29/A18/SCL1_29") (pintype "bidirectional"))
    )
    (net (code "47") (name "NUSE2") (class "Default")
      (node (ref "QUANTUM_CONNECTOR") (pin "22") (pinfunction "22_22") (pintype "passive"))
      (node (ref "TEENSY3.2_2") (pin "16/A2") (pinfunction "16/A2/T_16/A2") (pintype "bidirectional"))
    )
    (net (code "48") (name "NUSE3") (class "Default")
      (node (ref "QUANTUM_CONNECTOR") (pin "24") (pinfunction "24_24") (pintype "passive"))
      (node (ref "TEENSY3.2_2") (pin "33") (pinfunction "33/T_33") (pintype "bidirectional"))
    )
    (net (code "49") (name "NUSE4") (class "Default")
      (node (ref "QUANTUM_CONNECTOR") (pin "13") (pinfunction "13_13") (pintype "passive"))
      (node (ref "TEENSY3.2_2") (pin "28") (pinfunction "28/A17_28") (pintype "bidirectional"))
    )
    (net (code "50") (name "Net-(LED1-PadC)") (class "Default")
      (node (ref "LED1") (pin "C") (pinfunction "C_C") (pintype "passive"))
      (node (ref "R10") (pin "2") (pinfunction "2_2") (pintype "passive"))
    )
    (net (code "51") (name "Net-(LED2-PadC)") (class "Default")
      (node (ref "LED2") (pin "C") (pinfunction "C_C") (pintype "passive"))
      (node (ref "R1") (pin "2") (pinfunction "2_2") (pintype "passive"))
    )
    (net (code "52") (name "Net-(LED3-PadC)") (class "Default")
      (node (ref "LED3") (pin "C") (pinfunction "C_C") (pintype "passive"))
      (node (ref "R14") (pin "2") (pinfunction "2_2") (pintype "passive"))
    )
    (net (code "53") (name "Net-(LED4-PadC)") (class "Default")
      (node (ref "LED4") (pin "C") (pinfunction "C_C") (pintype "passive"))
      (node (ref "R13") (pin "2") (pinfunction "2_2") (pintype "passive"))
    )
    (net (code "54") (name "Net-(LED5-PadC)") (class "Default")
      (node (ref "LED5") (pin "C") (pinfunction "C_C") (pintype "passive"))
      (node (ref "R4") (pin "2") (pinfunction "2_2") (pintype "passive"))
    )
    (net (code "55") (name "Net-(LED6-PadC)") (class "Default")
      (node (ref "LED6") (pin "C") (pinfunction "C_C") (pintype "passive"))
      (node (ref "R11") (pin "2") (pinfunction "2_2") (pintype "passive"))
    )
    (net (code "56") (name "Net-(LED7-PadC)") (class "Default")
      (node (ref "LED7") (pin "C") (pinfunction "C_C") (pintype "passive"))
      (node (ref "R16") (pin "2") (pinfunction "2_2") (pintype "passive"))
    )
    (net (code "57") (name "Net-(LED8-PadC)") (class "Default")
      (node (ref "LED8") (pin "C") (pinfunction "C_C") (pintype "passive"))
      (node (ref "R17") (pin "2") (pinfunction "2_2") (pintype "passive"))
    )
    (net (code "58") (name "Net-(LED_3.3-PadC)") (class "Default")
      (node (ref "LED_3.3") (pin "C") (pinfunction "C_C") (pintype "passive"))
      (node (ref "R7") (pin "2") (pinfunction "2_2") (pintype "passive"))
    )
    (net (code "59") (name "Net-(LED_5-PadC)") (class "Default")
      (node (ref "LED_5") (pin "C") (pinfunction "C_C") (pintype "passive"))
      (node (ref "R3") (pin "2") (pinfunction "2_2") (pintype "passive"))
    )
    (net (code "60") (name "Net-(LED_RGB-BLUE_A)") (class "Default")
      (node (ref "LED_RGB") (pin "3") (pinfunction "BLUE_A_3") (pintype "bidirectional"))
      (node (ref "R5") (pin "1") (pinfunction "1_1") (pintype "passive"))
    )
    (net (code "61") (name "Net-(LED_RGB-GREEN_A)") (class "Default")
      (node (ref "LED_RGB") (pin "1") (pinfunction "GREEN_A_1") (pintype "bidirectional"))
      (node (ref "R8") (pin "1") (pinfunction "1_1") (pintype "passive"))
    )
    (net (code "62") (name "Net-(LED_RGB-RED_A)") (class "Default")
      (node (ref "LED_RGB") (pin "2") (pinfunction "RED_A_2") (pintype "bidirectional"))
      (node (ref "R9") (pin "1") (pinfunction "1_1") (pintype "passive"))
    )
    (net (code "63") (name "Net-(R6-Pad1)") (class "Default")
      (node (ref "R6") (pin "1") (pinfunction "1_1") (pintype "passive"))
      (node (ref "SW") (pin "5") (pinfunction "5_5") (pintype "passive"))
    )
    (net (code "64") (name "Net-(R62-Pad1)") (class "Default")
      (node (ref "R62") (pin "1") (pinfunction "1_1") (pintype "passive"))
      (node (ref "SW") (pin "8") (pinfunction "8_8") (pintype "passive"))
    )
    (net (code "65") (name "Net-(R63-Pad2)") (class "Default")
      (node (ref "R63") (pin "2") (pinfunction "2_2") (pintype "passive"))
      (node (ref "SW") (pin "7") (pinfunction "7_7") (pintype "passive"))
    )
    (net (code "66") (name "Net-(R64-Pad2)") (class "Default")
      (node (ref "R64") (pin "2") (pinfunction "2_2") (pintype "passive"))
      (node (ref "SW") (pin "6") (pinfunction "6_6") (pintype "passive"))
    )
    (net (code "67") (name "PROGRAM") (class "Default")
      (node (ref "PROGRAM") (pin "A2") (pinfunction "1_A2") (pintype "passive"))
      (node (ref "USB_2") (pin "5") (pinfunction "5_5") (pintype "passive"))
    )
    (net (code "68") (name "PULS") (class "Default")
      (node (ref "C57") (pin "2") (pinfunction "2_2") (pintype "passive"))
      (node (ref "ENCODER") (pin "B") (pinfunction "B_B") (pintype "passive"))
      (node (ref "TEENSY3.2_2") (pin "23/A9") (pinfunction "23/A9/T/PWM_23/A9") (pintype "bidirectional"))
    )
    (net (code "69") (name "PWM1") (class "Default")
      (node (ref "QUANTUM_CONNECTOR") (pin "4") (pinfunction "4_4") (pintype "passive"))
      (node (ref "TEENSY3.2_2") (pin "5") (pinfunction "5/PWM_5") (pintype "bidirectional"))
    )
    (net (code "70") (name "PWM2") (class "Default")
      (node (ref "QUANTUM_CONNECTOR") (pin "10") (pinfunction "10_10") (pintype "passive"))
      (node (ref "TEENSY3.2_2") (pin "9") (pinfunction "9/RX2/PWM_9") (pintype "bidirectional"))
    )
    (net (code "71") (name "PWM3") (class "Default")
      (node (ref "QUANTUM_CONNECTOR") (pin "9") (pinfunction "9_9") (pintype "passive"))
      (node (ref "TEENSY3.2_2") (pin "32") (pinfunction "32/T/PWM_32") (pintype "bidirectional"))
    )
    (net (code "72") (name "PWM4") (class "Default")
      (node (ref "QUANTUM_CONNECTOR") (pin "3") (pinfunction "3_3") (pintype "passive"))
      (node (ref "TEENSY3.2_2") (pin "4") (pinfunction "4/CAN-RX-PWM_4") (pintype "bidirectional"))
    )
    (net (code "73") (name "RED") (class "Default")
      (node (ref "R9") (pin "2") (pinfunction "2_2") (pintype "passive"))
      (node (ref "TEENSY3.2_2") (pin "20/A6") (pinfunction "20/A6/PWM_20/A6") (pintype "bidirectional"))
    )
    (net (code "74") (name "RESET") (class "Default")
      (node (ref "SPI") (pin "5") (pinfunction "5_5") (pintype "passive"))
    )
    (net (code "75") (name "SCK") (class "Default")
      (node (ref "DISPLAY1") (pin "SCK") (pinfunction "SCK_SCK") (pintype "bidirectional"))
      (node (ref "SPI") (pin "3") (pinfunction "3_3") (pintype "passive"))
      (node (ref "TEENSY3.2_2") (pin "13") (pinfunction "13/SCK/LED_13") (pintype "bidirectional"))
    )
    (net (code "76") (name "SCL") (class "Default")
      (node (ref "R65") (pin "1") (pinfunction "1_1") (pintype "passive"))
      (node (ref "TEENSY3.2_2") (pin "19/A5") (pinfunction "19/A5/T/SCL0_19/A5") (pintype "bidirectional"))
      (node (ref "U$5") (pin "SCL") (pinfunction "SCL_SCL") (pintype "bidirectional"))
    )
    (net (code "77") (name "SDA") (class "Default")
      (node (ref "R66") (pin "1") (pinfunction "1_1") (pintype "passive"))
      (node (ref "TEENSY3.2_2") (pin "18/A4") (pinfunction "18/A4/T/SDA0_18/A4") (pintype "bidirectional"))
      (node (ref "U$5") (pin "SDA") (pinfunction "SDA_SDA") (pintype "bidirectional"))
    )
    (net (code "78") (name "SEL") (class "Default")
      (node (ref "ENCODER") (pin "E") (pinfunction "2_E") (pintype "passive"))
      (node (ref "TEENSY3.2_2") (pin "A11") (pinfunction "A11_A11") (pintype "bidirectional"))
    )
    (net (code "79") (name "SPEED") (class "Default")
      (node (ref "R12") (pin "S") (pinfunction "S_S") (pintype "passive"))
      (node (ref "TEENSY3.2_2") (pin "A12") (pinfunction "A12_A12") (pintype "bidirectional"))
    )
    (net (code "80") (name "TEENSY1-RX_TEENSY2-TX") (class "Default")
      (node (ref "QUANTUM_CONNECTOR") (pin "29") (pinfunction "29_29") (pintype "passive"))
      (node (ref "TEENSY3.2_2") (pin "1") (pinfunction "1/TX1/T_1") (pintype "bidirectional"))
    )
    (net (code "81") (name "TEENSY1-TX_TEENSY2-RX") (class "Default")
      (node (ref "QUANTUM_CONNECTOR") (pin "30") (pinfunction "30_30") (pintype "passive"))
      (node (ref "TEENSY3.2_2") (pin "0") (pinfunction "0/RX1/T_0") (pintype "bidirectional"))
    )
    (net (code "82") (name "TONE") (class "Default")
      (node (ref "BUZZER") (pin "+") (pinfunction "1_+") (pintype "passive"))
      (node (ref "TEENSY3.2_2") (pin "RESET/DAC") (pinfunction "A14/DAC_RESET/DAC") (pintype "bidirectional"))
    )
    (net (code "83") (name "VBATTEENSY") (class "Default")
      (node (ref "TEENSY3.2_2") (pin "VBAT") (pinfunction "VBAT_VBAT") (pintype "power_in"))
    )
    (net (code "84") (name "VIN") (class "Default")
      (node (ref "TEENSY3.2_2") (pin "VIN") (pinfunction "VIN_VIN") (pintype "power_in"))
    )
    (net (code "85") (name "VUSB") (class "Default")
      (node (ref "USB") (pin "VBUS") (pinfunction "VBUS_VBUS") (pintype "bidirectional"))
      (node (ref "USB_2") (pin "1") (pinfunction "1_1") (pintype "passive"))
    )
    (net (code "86") (name "unconnected-(IC2-QH*-Pad9)") (class "Default")
      (node (ref "IC2") (pin "9") (pinfunction "QH*_9") (pintype "tri_state"))
    )
    (net (code "87") (name "unconnected-(TEENSY3.2_2-PadPGM)") (class "Default")
      (node (ref "TEENSY3.2_2") (pin "PGM") (pinfunction "PGM_PGM") (pintype "bidirectional"))
    )
    (net (code "88") (name "unconnected-(TEENSY3.2_2-PadVUSB)") (class "Default")
      (node (ref "TEENSY3.2_2") (pin "VUSB") (pinfunction "VUSB_VUSB") (pintype "power_in"))
    )
    (net (code "89") (name "unconnected-(U$9-PadCS_I)") (class "Default")
      (node (ref "U$9") (pin "CS_I") (pinfunction "CS_I_CS_I") (pintype "no_connect"))
    )
    (net (code "90") (name "unconnected-(U$9-PadRST)") (class "Default")
      (node (ref "U$9") (pin "RST") (pinfunction "RST_RST") (pintype "no_connect"))
    )
  )
)
